# circuit_0_3_1.net
KiCad netlist of a schematic drawn in EAGLE
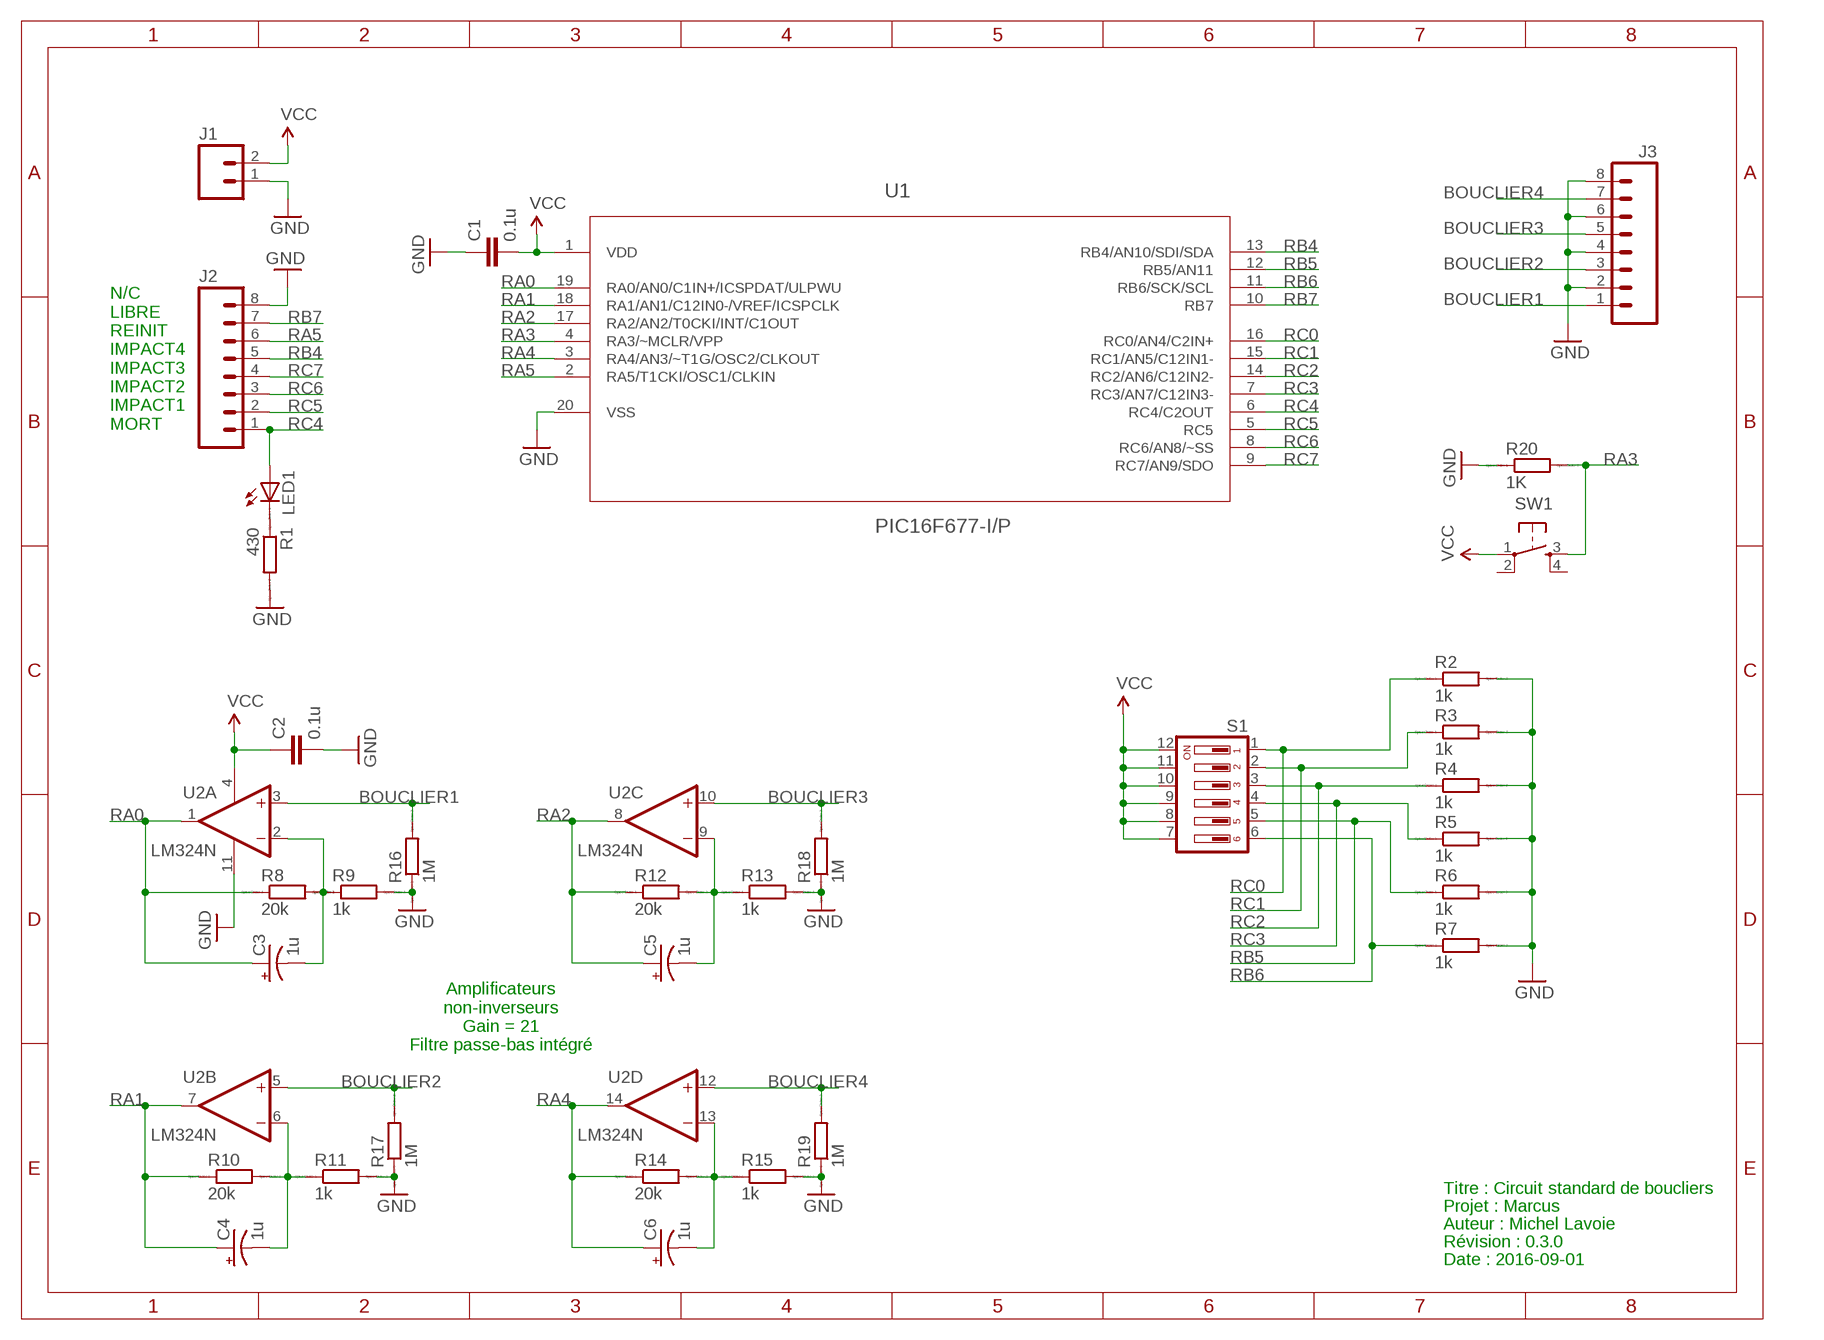
[diagram p0: schematic, sheet 1]

(export (version "E")
  (design (tool "Eeschema 10.0.6"))
  (components
    (comp (ref "C1")
      (value "0.1u")
      (footprint "eagle-import:CAP-PTH-SMALL")
      (libsource (lib "eagle-import") (part "CAPPTH"))
    )
    (comp (ref "C2")
      (value "0.1u")
      (footprint "eagle-import:CAP-PTH-SMALL")
      (libsource (lib "eagle-import") (part "CAPPTH"))
    )
    (comp (ref "C3")
      (value "1u")
      (footprint "eagle-import:E2,5-5")
      (libsource (lib "eagle-import") (part "CPOL-USE2.5-5"))
    )
    (comp (ref "C4")
      (value "1u")
      (footprint "eagle-import:E2,5-5")
      (libsource (lib "eagle-import") (part "CPOL-USE2.5-5"))
    )
    (comp (ref "C5")
      (value "1u")
      (footprint "eagle-import:E2,5-5")
      (libsource (lib "eagle-import") (part "CPOL-USE2.5-5"))
    )
    (comp (ref "C6")
      (value "1u")
      (footprint "eagle-import:E2,5-5")
      (libsource (lib "eagle-import") (part "CPOL-USE2.5-5"))
    )
    (comp (ref "J1")
      (value "M02PTH")
      (footprint "eagle-import:1X02")
      (libsource (lib "eagle-import") (part "M02PTH"))
    )
    (comp (ref "J2")
      (value "M08NO_SILK")
      (footprint "eagle-import:1X08_PIN1_NO_SILK")
      (libsource (lib "eagle-import") (part "M08NO_SILK"))
    )
    (comp (ref "J3")
      (value "M08NO_SILK")
      (footprint "eagle-import:1X08_PIN1_NO_SILK")
      (libsource (lib "eagle-import") (part "M08NO_SILK"))
    )
    (comp (ref "LED1")
      (value "LED3MM")
      (footprint "eagle-import:LED3MM")
      (libsource (lib "eagle-import") (part "LED3MM"))
    )
    (comp (ref "R1")
      (value "430")
      (footprint "eagle-import:0207_10")
      (libsource (lib "eagle-import") (part "R0207/10"))
    )
    (comp (ref "R2")
      (value "1k")
      (footprint "eagle-import:0207_10")
      (libsource (lib "eagle-import") (part "R0207/10"))
    )
    (comp (ref "R3")
      (value "1k")
      (footprint "eagle-import:0207_10")
      (libsource (lib "eagle-import") (part "R0207/10"))
    )
    (comp (ref "R4")
      (value "1k")
      (footprint "eagle-import:0207_10")
      (libsource (lib "eagle-import") (part "R0207/10"))
    )
    (comp (ref "R5")
      (value "1k")
      (footprint "eagle-import:0207_10")
      (libsource (lib "eagle-import") (part "R0207/10"))
    )
    (comp (ref "R6")
      (value "1k")
      (footprint "eagle-import:0207_10")
      (libsource (lib "eagle-import") (part "R0207/10"))
    )
    (comp (ref "R7")
      (value "1k")
      (footprint "eagle-import:0207_10")
      (libsource (lib "eagle-import") (part "R0207/10"))
    )
    (comp (ref "R8")
      (value "20k")
      (footprint "eagle-import:0207_10")
      (libsource (lib "eagle-import") (part "R0207/10"))
    )
    (comp (ref "R9")
      (value "1k")
      (footprint "eagle-import:0207_10")
      (libsource (lib "eagle-import") (part "R0207/10"))
    )
    (comp (ref "R10")
      (value "20k")
      (footprint "eagle-import:0207_10")
      (libsource (lib "eagle-import") (part "R0207/10"))
    )
    (comp (ref "R11")
      (value "1k")
      (footprint "eagle-import:0207_10")
      (libsource (lib "eagle-import") (part "R0207/10"))
    )
    (comp (ref "R12")
      (value "20k")
      (footprint "eagle-import:0207_10")
      (libsource (lib "eagle-import") (part "R0207/10"))
    )
    (comp (ref "R13")
      (value "1k")
      (footprint "eagle-import:0207_10")
      (libsource (lib "eagle-import") (part "R0207/10"))
    )
    (comp (ref "R14")
      (value "20k")
      (footprint "eagle-import:0207_10")
      (libsource (lib "eagle-import") (part "R0207/10"))
    )
    (comp (ref "R15")
      (value "1k")
      (footprint "eagle-import:0207_10")
      (libsource (lib "eagle-import") (part "R0207/10"))
    )
    (comp (ref "R16")
      (value "1M")
      (footprint "eagle-import:0207_10")
      (libsource (lib "eagle-import") (part "R0207/10"))
    )
    (comp (ref "R17")
      (value "1M")
      (footprint "eagle-import:0207_10")
      (libsource (lib "eagle-import") (part "R0207/10"))
    )
    (comp (ref "R18")
      (value "1M")
      (footprint "eagle-import:0207_10")
      (libsource (lib "eagle-import") (part "R0207/10"))
    )
    (comp (ref "R19")
      (value "1M")
      (footprint "eagle-import:0207_10")
      (libsource (lib "eagle-import") (part "R0207/10"))
    )
    (comp (ref "R20")
      (value "1K")
      (footprint "eagle-import:0207_10")
      (libsource (lib "eagle-import") (part "R0207/10"))
    )
    (comp (ref "S1")
      (value "DIP06YL")
      (footprint "eagle-import:DIP06YL")
      (libsource (lib "eagle-import") (part "DIP06YL"))
    )
    (comp (ref "SW1")
      (value "TAC_SWITCHPTH")
      (footprint "eagle-import:TACTILE-PTH")
      (libsource (lib "eagle-import") (part "TAC_SWITCHPTH"))
    )
    (comp (ref "U1")
      (value "PIC16F677-I/P")
      (footprint "eagle-import:DIP254P762X533-20")
      (libsource (lib "eagle-import") (part "PIC16F677-I/P"))
    )
    (comp (ref "U2")
      (value "LM324N")
      (footprint "eagle-import:DIL14")
      (libsource (lib "eagle-import") (part "LM324N"))
    )
  )
  (nets
    (net (code "1") (name "/BOUCLIER1") (class "Default")
      (node (ref "J3") (pin "1") (pinfunction "1_1") (pintype "passive"))
      (node (ref "R16") (pin "2") (pinfunction "2_2") (pintype "passive"))
      (node (ref "U2") (pin "3") (pinfunction "+IN_3") (pintype "input"))
    )
    (net (code "2") (name "/BOUCLIER2") (class "Default")
      (node (ref "J3") (pin "3") (pinfunction "3_3") (pintype "passive"))
      (node (ref "R17") (pin "2") (pinfunction "2_2") (pintype "passive"))
      (node (ref "U2") (pin "5") (pinfunction "+IN_5") (pintype "input"))
    )
    (net (code "3") (name "/BOUCLIER3") (class "Default")
      (node (ref "J3") (pin "5") (pinfunction "5_5") (pintype "passive"))
      (node (ref "R18") (pin "2") (pinfunction "2_2") (pintype "passive"))
      (node (ref "U2") (pin "10") (pinfunction "+IN_10") (pintype "input"))
    )
    (net (code "4") (name "/BOUCLIER4") (class "Default")
      (node (ref "J3") (pin "7") (pinfunction "7_7") (pintype "passive"))
      (node (ref "R19") (pin "2") (pinfunction "2_2") (pintype "passive"))
      (node (ref "U2") (pin "12") (pinfunction "+IN_12") (pintype "input"))
    )
    (net (code "5") (name "/RA0") (class "Default")
      (node (ref "C3") (pin "+") (pinfunction "+_+") (pintype "passive"))
      (node (ref "R8") (pin "1") (pinfunction "1_1") (pintype "passive"))
      (node (ref "U1") (pin "19") (pinfunction "RA0/AN0/C1IN+/ICSPDAT/ULPWU_19") (pintype "bidirectional"))
      (node (ref "U2") (pin "1") (pinfunction "OUT_1") (pintype "output"))
    )
    (net (code "6") (name "/RA1") (class "Default")
      (node (ref "C4") (pin "+") (pinfunction "+_+") (pintype "passive"))
      (node (ref "R10") (pin "1") (pinfunction "1_1") (pintype "passive"))
      (node (ref "U1") (pin "18") (pinfunction "RA1/AN1/C12IN0-/VREF/ICSPCLK_18") (pintype "bidirectional"))
      (node (ref "U2") (pin "7") (pinfunction "OUT_7") (pintype "output"))
    )
    (net (code "7") (name "/RA2") (class "Default")
      (node (ref "C5") (pin "+") (pinfunction "+_+") (pintype "passive"))
      (node (ref "R12") (pin "1") (pinfunction "1_1") (pintype "passive"))
      (node (ref "U1") (pin "17") (pinfunction "RA2/AN2/T0CKI/INT/C1OUT_17") (pintype "bidirectional"))
      (node (ref "U2") (pin "8") (pinfunction "OUT_8") (pintype "output"))
    )
    (net (code "8") (name "/RA3") (class "Default")
      (node (ref "R20") (pin "2") (pinfunction "2_2") (pintype "passive"))
      (node (ref "SW1") (pin "3") (pinfunction "3_3") (pintype "passive"))
      (node (ref "U1") (pin "4") (pinfunction "RA3/~{MCLR/VPP}_4") (pintype "bidirectional"))
    )
    (net (code "9") (name "/RA4") (class "Default")
      (node (ref "C6") (pin "+") (pinfunction "+_+") (pintype "passive"))
      (node (ref "R14") (pin "1") (pinfunction "1_1") (pintype "passive"))
      (node (ref "U1") (pin "3") (pinfunction "RA4/AN3/~{T1G/OSC2/CLKOUT}_3") (pintype "bidirectional"))
      (node (ref "U2") (pin "14") (pinfunction "OUT_14") (pintype "output"))
    )
    (net (code "10") (name "/RA5") (class "Default")
      (node (ref "J2") (pin "6") (pinfunction "6_6") (pintype "passive"))
      (node (ref "U1") (pin "2") (pinfunction "RA5/T1CKI/OSC1/CLKIN_2") (pintype "bidirectional"))
    )
    (net (code "11") (name "/RB4") (class "Default")
      (node (ref "J2") (pin "5") (pinfunction "5_5") (pintype "passive"))
      (node (ref "U1") (pin "13") (pinfunction "RB4/AN10/SDI/SDA_13") (pintype "bidirectional"))
    )
    (net (code "12") (name "/RB5") (class "Default")
      (node (ref "R6") (pin "1") (pinfunction "1_1") (pintype "passive"))
      (node (ref "S1") (pin "5") (pinfunction "5_5") (pintype "passive"))
      (node (ref "U1") (pin "12") (pinfunction "RB5/AN11_12") (pintype "bidirectional"))
    )
    (net (code "13") (name "/RB6") (class "Default")
      (node (ref "R7") (pin "1") (pinfunction "1_1") (pintype "passive"))
      (node (ref "S1") (pin "6") (pinfunction "6_6") (pintype "passive"))
      (node (ref "U1") (pin "11") (pinfunction "RB6/SCK/SCL_11") (pintype "bidirectional"))
    )
    (net (code "14") (name "/RB7") (class "Default")
      (node (ref "J2") (pin "7") (pinfunction "7_7") (pintype "passive"))
      (node (ref "U1") (pin "10") (pinfunction "RB7_10") (pintype "bidirectional"))
    )
    (net (code "15") (name "/RC0") (class "Default")
      (node (ref "R2") (pin "1") (pinfunction "1_1") (pintype "passive"))
      (node (ref "S1") (pin "1") (pinfunction "1_1") (pintype "passive"))
      (node (ref "U1") (pin "16") (pinfunction "RC0/AN4/C2IN+_16") (pintype "bidirectional"))
    )
    (net (code "16") (name "/RC1") (class "Default")
      (node (ref "R3") (pin "1") (pinfunction "1_1") (pintype "passive"))
      (node (ref "S1") (pin "2") (pinfunction "2_2") (pintype "passive"))
      (node (ref "U1") (pin "15") (pinfunction "RC1/AN5/C12IN1-_15") (pintype "bidirectional"))
    )
    (net (code "17") (name "/RC2") (class "Default")
      (node (ref "R4") (pin "1") (pinfunction "1_1") (pintype "passive"))
      (node (ref "S1") (pin "3") (pinfunction "3_3") (pintype "passive"))
      (node (ref "U1") (pin "14") (pinfunction "RC2/AN6/C12IN2-_14") (pintype "bidirectional"))
    )
    (net (code "18") (name "/RC3") (class "Default")
      (node (ref "R5") (pin "1") (pinfunction "1_1") (pintype "passive"))
      (node (ref "S1") (pin "4") (pinfunction "4_4") (pintype "passive"))
      (node (ref "U1") (pin "7") (pinfunction "RC3/AN7/C12IN3-_7") (pintype "bidirectional"))
    )
    (net (code "19") (name "/RC4") (class "Default")
      (node (ref "J2") (pin "1") (pinfunction "1_1") (pintype "passive"))
      (node (ref "LED1") (pin "A") (pinfunction "A_A") (pintype "passive"))
      (node (ref "U1") (pin "6") (pinfunction "RC4/C2OUT_6") (pintype "bidirectional"))
    )
    (net (code "20") (name "/RC5") (class "Default")
      (node (ref "J2") (pin "2") (pinfunction "2_2") (pintype "passive"))
      (node (ref "U1") (pin "5") (pinfunction "RC5_5") (pintype "bidirectional"))
    )
    (net (code "21") (name "/RC6") (class "Default")
      (node (ref "J2") (pin "3") (pinfunction "3_3") (pintype "passive"))
      (node (ref "U1") (pin "8") (pinfunction "RC6/AN8/~{SS}_8") (pintype "bidirectional"))
    )
    (net (code "22") (name "/RC7") (class "Default")
      (node (ref "J2") (pin "4") (pinfunction "4_4") (pintype "passive"))
      (node (ref "U1") (pin "9") (pinfunction "RC7/AN9/SDO_9") (pintype "bidirectional"))
    )
    (net (code "23") (name "GND") (class "Default")
      (node (ref "C1") (pin "1") (pinfunction "1_1") (pintype "passive"))
      (node (ref "C2") (pin "2") (pinfunction "2_2") (pintype "passive"))
      (node (ref "J1") (pin "1") (pinfunction "1_1") (pintype "passive"))
      (node (ref "J2") (pin "8") (pinfunction "8_8") (pintype "passive"))
      (node (ref "J3") (pin "2") (pinfunction "2_2") (pintype "passive"))
      (node (ref "J3") (pin "4") (pinfunction "4_4") (pintype "passive"))
      (node (ref "J3") (pin "6") (pinfunction "6_6") (pintype "passive"))
      (node (ref "J3") (pin "8") (pinfunction "8_8") (pintype "passive"))
      (node (ref "R1") (pin "2") (pinfunction "2_2") (pintype "passive"))
      (node (ref "R11") (pin "2") (pinfunction "2_2") (pintype "passive"))
      (node (ref "R13") (pin "2") (pinfunction "2_2") (pintype "passive"))
      (node (ref "R15") (pin "2") (pinfunction "2_2") (pintype "passive"))
      (node (ref "R16") (pin "1") (pinfunction "1_1") (pintype "passive"))
      (node (ref "R17") (pin "1") (pinfunction "1_1") (pintype "passive"))
      (node (ref "R18") (pin "1") (pinfunction "1_1") (pintype "passive"))
      (node (ref "R19") (pin "1") (pinfunction "1_1") (pintype "passive"))
      (node (ref "R2") (pin "2") (pinfunction "2_2") (pintype "passive"))
      (node (ref "R20") (pin "1") (pinfunction "1_1") (pintype "passive"))
      (node (ref "R3") (pin "2") (pinfunction "2_2") (pintype "passive"))
      (node (ref "R4") (pin "2") (pinfunction "2_2") (pintype "passive"))
      (node (ref "R5") (pin "2") (pinfunction "2_2") (pintype "passive"))
      (node (ref "R6") (pin "2") (pinfunction "2_2") (pintype "passive"))
      (node (ref "R7") (pin "2") (pinfunction "2_2") (pintype "passive"))
      (node (ref "R9") (pin "2") (pinfunction "2_2") (pintype "passive"))
      (node (ref "U1") (pin "20") (pinfunction "VSS_20") (pintype "power_in"))
      (node (ref "U2") (pin "11") (pinfunction "V-_11") (pintype "power_in"))
    )
    (net (code "24") (name "Net-(LED1-C)") (class "Default")
      (node (ref "LED1") (pin "K") (pinfunction "C_K") (pintype "passive"))
      (node (ref "R1") (pin "1") (pinfunction "1_1") (pintype "passive"))
    )
    (net (code "25") (name "Net-(U2A--IN)") (class "Default")
      (node (ref "C3") (pin "-") (pinfunction "-_-") (pintype "passive"))
      (node (ref "R8") (pin "2") (pinfunction "2_2") (pintype "passive"))
      (node (ref "R9") (pin "1") (pinfunction "1_1") (pintype "passive"))
      (node (ref "U2") (pin "2") (pinfunction "-IN_2") (pintype "input"))
    )
    (net (code "26") (name "Net-(U2B--IN)") (class "Default")
      (node (ref "C4") (pin "-") (pinfunction "-_-") (pintype "passive"))
      (node (ref "R10") (pin "2") (pinfunction "2_2") (pintype "passive"))
      (node (ref "R11") (pin "1") (pinfunction "1_1") (pintype "passive"))
      (node (ref "U2") (pin "6") (pinfunction "-IN_6") (pintype "input"))
    )
    (net (code "27") (name "Net-(U2C--IN)") (class "Default")
      (node (ref "C5") (pin "-") (pinfunction "-_-") (pintype "passive"))
      (node (ref "R12") (pin "2") (pinfunction "2_2") (pintype "passive"))
      (node (ref "R13") (pin "1") (pinfunction "1_1") (pintype "passive"))
      (node (ref "U2") (pin "9") (pinfunction "-IN_9") (pintype "input"))
    )
    (net (code "28") (name "Net-(U2D--IN)") (class "Default")
      (node (ref "C6") (pin "-") (pinfunction "-_-") (pintype "passive"))
      (node (ref "R14") (pin "2") (pinfunction "2_2") (pintype "passive"))
      (node (ref "R15") (pin "1") (pinfunction "1_1") (pintype "passive"))
      (node (ref "U2") (pin "13") (pinfunction "-IN_13") (pintype "input"))
    )
    (net (code "29") (name "VCC") (class "Default")
      (node (ref "C1") (pin "2") (pinfunction "2_2") (pintype "passive"))
      (node (ref "C2") (pin "1") (pinfunction "1_1") (pintype "passive"))
      (node (ref "J1") (pin "2") (pinfunction "2_2") (pintype "passive"))
      (node (ref "S1") (pin "10") (pinfunction "10_10") (pintype "passive"))
      (node (ref "S1") (pin "11") (pinfunction "11_11") (pintype "passive"))
      (node (ref "S1") (pin "12") (pinfunction "12_12") (pintype "passive"))
      (node (ref "S1") (pin "7") (pinfunction "7_7") (pintype "passive"))
      (node (ref "S1") (pin "8") (pinfunction "8_8") (pintype "passive"))
      (node (ref "S1") (pin "9") (pinfunction "9_9") (pintype "passive"))
      (node (ref "SW1") (pin "1") (pinfunction "1_1") (pintype "passive"))
      (node (ref "U1") (pin "1") (pinfunction "VDD_1") (pintype "power_in"))
      (node (ref "U2") (pin "4") (pinfunction "V+_4") (pintype "power_in"))
    )
    (net (code "30") (name "unconnected-(SW1-Pad2)") (class "Default")
      (node (ref "SW1") (pin "2") (pinfunction "2_2") (pintype "passive"))
    )
    (net (code "31") (name "unconnected-(SW1-Pad4)") (class "Default")
      (node (ref "SW1") (pin "4") (pinfunction "4_4") (pintype "passive"))
    )
  )
)
